# placa2caras_V1718.net
KiCad netlist of a schematic drawn in EAGLE
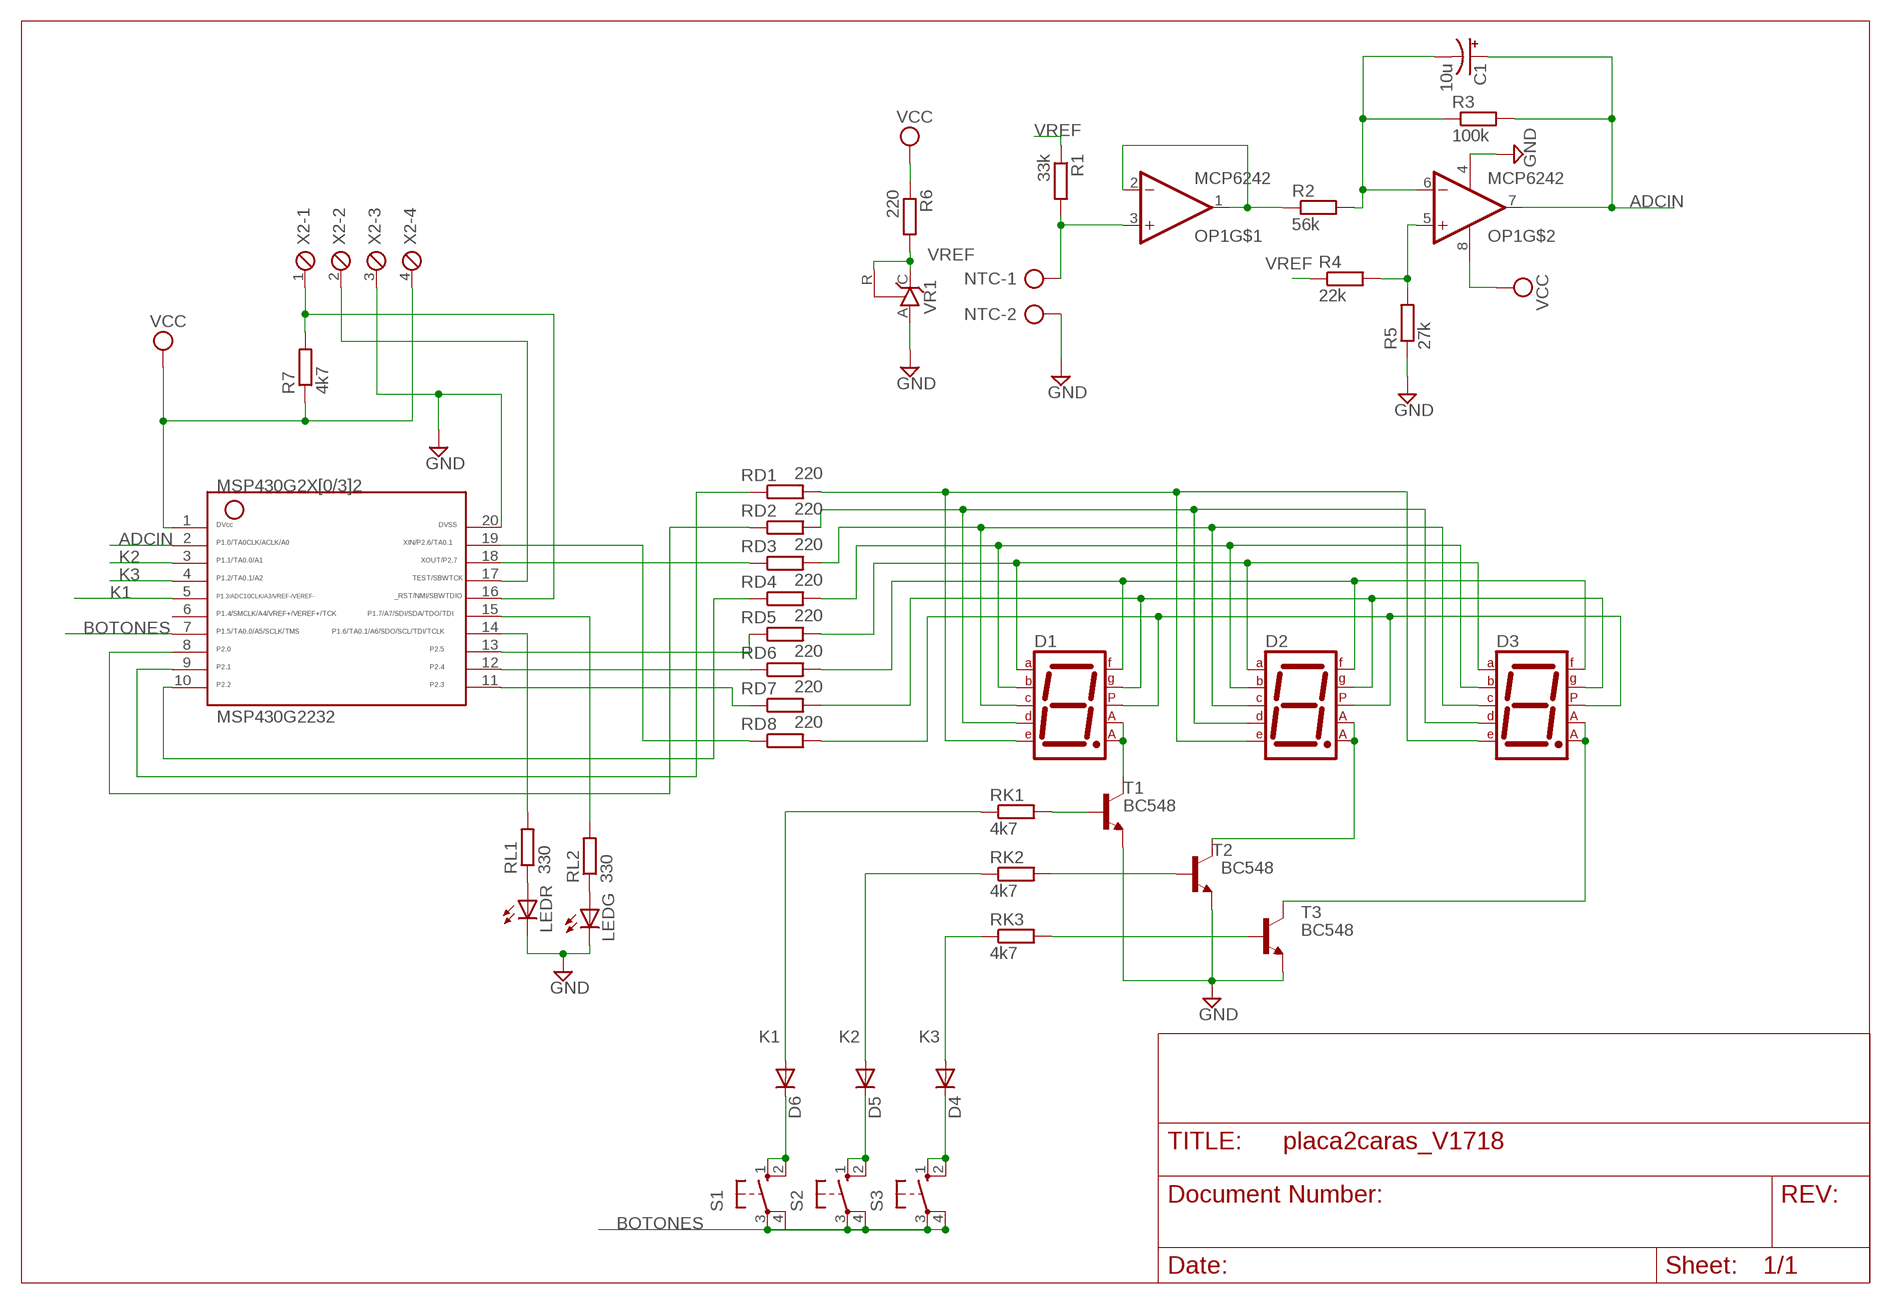
[diagram p0: schematic, sheet 1]

(export (version "E")
  (design (tool "Eeschema 10.0.6"))
  (components
    (comp (ref "C1")
      (value "10u")
      (footprint "eagle-import:E2,5-6E")
      (libsource (lib "eagle-import") (part "CPOL-USE2,5-6E"))
    )
    (comp (ref "D1")
      (value "7SEG-CA")
      (footprint "eagle-import:7SEG-13")
      (libsource (lib "eagle-import") (part "7SEG-CA"))
    )
    (comp (ref "D2")
      (value "7SEG-CA")
      (footprint "eagle-import:7SEG-13")
      (libsource (lib "eagle-import") (part "7SEG-CA"))
    )
    (comp (ref "D3")
      (value "7SEG-CA")
      (footprint "eagle-import:7SEG-13")
      (libsource (lib "eagle-import") (part "7SEG-CA"))
    )
    (comp (ref "D4")
      (value "1N4148DO35-10")
      (footprint "eagle-import:DO35-10")
      (libsource (lib "eagle-import") (part "1N4148DO35-10"))
    )
    (comp (ref "D5")
      (value "1N4148DO35-10")
      (footprint "eagle-import:DO35-10")
      (libsource (lib "eagle-import") (part "1N4148DO35-10"))
    )
    (comp (ref "D6")
      (value "1N4148DO35-10")
      (footprint "eagle-import:DO35-10")
      (libsource (lib "eagle-import") (part "1N4148DO35-10"))
    )
    (comp (ref "LEDG")
      (value "LED5MM")
      (footprint "eagle-import:LED5MM")
      (libsource (lib "eagle-import") (part "LED5MM"))
    )
    (comp (ref "LEDR")
      (value "LED5MM")
      (footprint "eagle-import:LED5MM")
      (libsource (lib "eagle-import") (part "LED5MM"))
    )
    (comp (ref "MSP430G2232")
      (value "G2X[0/3]2---N20")
      (footprint "eagle-import:N20")
      (libsource (lib "eagle-import") (part "G2X[0/3]2---N20"))
    )
    (comp (ref "NTC")
      (value "AK500/2")
      (footprint "eagle-import:AK500_2")
      (libsource (lib "eagle-import") (part "AK500/2"))
    )
    (comp (ref "OP1")
      (value "MCP6242")
      (footprint "eagle-import:DIL8_MOD")
      (libsource (lib "eagle-import") (part "MCP6242CONPADGORDO"))
    )
    (comp (ref "R1")
      (value "33k")
      (footprint "eagle-import:0207_10")
      (libsource (lib "eagle-import") (part "R-EU_0207/10"))
    )
    (comp (ref "R2")
      (value "56k")
      (footprint "eagle-import:0207_10")
      (libsource (lib "eagle-import") (part "R-EU_0207/10"))
    )
    (comp (ref "R3")
      (value "100k")
      (footprint "eagle-import:0207_10")
      (libsource (lib "eagle-import") (part "R-EU_0207/10"))
    )
    (comp (ref "R4")
      (value "22k")
      (footprint "eagle-import:0207_10")
      (libsource (lib "eagle-import") (part "R-EU_0207/10"))
    )
    (comp (ref "R5")
      (value "27k")
      (footprint "eagle-import:0207_10")
      (libsource (lib "eagle-import") (part "R-EU_0207/10"))
    )
    (comp (ref "R6")
      (value "220")
      (footprint "eagle-import:0207_10")
      (libsource (lib "eagle-import") (part "R-EU_0207/10"))
    )
    (comp (ref "R7")
      (value "4k7")
      (footprint "eagle-import:0207_10")
      (libsource (lib "eagle-import") (part "R-EU_0207/10"))
    )
    (comp (ref "RD1")
      (value "220")
      (footprint "eagle-import:0207_10")
      (libsource (lib "eagle-import") (part "R-EU_0207/10"))
    )
    (comp (ref "RD2")
      (value "220")
      (footprint "eagle-import:0207_10")
      (libsource (lib "eagle-import") (part "R-EU_0207/10"))
    )
    (comp (ref "RD3")
      (value "220")
      (footprint "eagle-import:0207_10")
      (libsource (lib "eagle-import") (part "R-EU_0207/10"))
    )
    (comp (ref "RD4")
      (value "220")
      (footprint "eagle-import:0207_10")
      (libsource (lib "eagle-import") (part "R-EU_0207/10"))
    )
    (comp (ref "RD5")
      (value "220")
      (footprint "eagle-import:0207_10")
      (libsource (lib "eagle-import") (part "R-EU_0207/10"))
    )
    (comp (ref "RD6")
      (value "220")
      (footprint "eagle-import:0207_10")
      (libsource (lib "eagle-import") (part "R-EU_0207/10"))
    )
    (comp (ref "RD7")
      (value "220")
      (footprint "eagle-import:0207_10")
      (libsource (lib "eagle-import") (part "R-EU_0207/10"))
    )
    (comp (ref "RD8")
      (value "220")
      (footprint "eagle-import:0207_10")
      (libsource (lib "eagle-import") (part "R-EU_0207/10"))
    )
    (comp (ref "RK1")
      (value "4k7")
      (footprint "eagle-import:0207_10")
      (libsource (lib "eagle-import") (part "R-EU_0207/10"))
    )
    (comp (ref "RK2")
      (value "4k7")
      (footprint "eagle-import:0207_10")
      (libsource (lib "eagle-import") (part "R-EU_0207/10"))
    )
    (comp (ref "RK3")
      (value "4k7")
      (footprint "eagle-import:0207_10")
      (libsource (lib "eagle-import") (part "R-EU_0207/10"))
    )
    (comp (ref "RL1")
      (value "330")
      (footprint "eagle-import:0207_10")
      (libsource (lib "eagle-import") (part "R-EU_0207/10"))
    )
    (comp (ref "RL2")
      (value "330")
      (footprint "eagle-import:0207_10")
      (libsource (lib "eagle-import") (part "R-EU_0207/10"))
    )
    (comp (ref "S1")
      (value "10-XX")
      (footprint "eagle-import:B3F-10XX")
      (fields (field (name "MPN") "B3F-1000"))
      (libsource (lib "eagle-import") (part "10-XX"))
    )
    (comp (ref "S2")
      (value "10-XX")
      (footprint "eagle-import:B3F-10XX")
      (fields (field (name "MPN") "B3F-1000"))
      (libsource (lib "eagle-import") (part "10-XX"))
    )
    (comp (ref "S3")
      (value "10-XX")
      (footprint "eagle-import:B3F-10XX")
      (fields (field (name "MPN") "B3F-1000"))
      (libsource (lib "eagle-import") (part "10-XX"))
    )
    (comp (ref "T1")
      (value "BC548")
      (footprint "eagle-import:TO92-EBC")
      (libsource (lib "eagle-import") (part "BC548"))
    )
    (comp (ref "T2")
      (value "BC548")
      (footprint "eagle-import:TO92-EBC")
      (libsource (lib "eagle-import") (part "BC548"))
    )
    (comp (ref "T3")
      (value "BC548")
      (footprint "eagle-import:TO92-EBC")
      (libsource (lib "eagle-import") (part "BC548"))
    )
    (comp (ref "VR1")
      (value "TL431CLP")
      (footprint "eagle-import:TO92-CLP")
      (libsource (lib "eagle-import") (part "TL431CLP"))
    )
    (comp (ref "X2")
      (value "MPT4")
      (footprint "eagle-import:4POL254")
      (libsource (lib "eagle-import") (part "MPT4"))
    )
  )
  (nets
    (net (code "1") (name "/ADCIN") (class "Default")
      (node (ref "C1") (pin "+") (pinfunction "+_+") (pintype "passive"))
      (node (ref "MSP430G2232") (pin "2") (pinfunction "2_2") (pintype "bidirectional"))
      (node (ref "OP1") (pin "7") (pinfunction "OUT_7") (pintype "output"))
      (node (ref "R3") (pin "2") (pinfunction "2_2") (pintype "passive"))
    )
    (net (code "2") (name "/BOTONES") (class "Default")
      (node (ref "MSP430G2232") (pin "7") (pinfunction "7_7") (pintype "bidirectional"))
      (node (ref "S1") (pin "3") (pinfunction "P_3") (pintype "passive"))
      (node (ref "S1") (pin "4") (pinfunction "P1_4") (pintype "passive"))
      (node (ref "S2") (pin "3") (pinfunction "P_3") (pintype "passive"))
      (node (ref "S2") (pin "4") (pinfunction "P1_4") (pintype "passive"))
      (node (ref "S3") (pin "3") (pinfunction "P_3") (pintype "passive"))
      (node (ref "S3") (pin "4") (pinfunction "P1_4") (pintype "passive"))
    )
    (net (code "3") (name "/K1") (class "Default")
      (node (ref "D6") (pin "A") (pinfunction "A_A") (pintype "passive"))
      (node (ref "MSP430G2232") (pin "5") (pinfunction "5_5") (pintype "bidirectional"))
      (node (ref "RK1") (pin "1") (pinfunction "1_1") (pintype "passive"))
    )
    (net (code "4") (name "/K2") (class "Default")
      (node (ref "D5") (pin "A") (pinfunction "A_A") (pintype "passive"))
      (node (ref "MSP430G2232") (pin "3") (pinfunction "3_3") (pintype "bidirectional"))
      (node (ref "RK2") (pin "1") (pinfunction "1_1") (pintype "passive"))
    )
    (net (code "5") (name "/K3") (class "Default")
      (node (ref "D4") (pin "A") (pinfunction "A_A") (pintype "passive"))
      (node (ref "MSP430G2232") (pin "4") (pinfunction "4_4") (pintype "bidirectional"))
      (node (ref "RK3") (pin "1") (pinfunction "1_1") (pintype "passive"))
    )
    (net (code "6") (name "/VREF") (class "Default")
      (node (ref "R1") (pin "1") (pinfunction "1_1") (pintype "passive"))
      (node (ref "R4") (pin "1") (pinfunction "1_1") (pintype "passive"))
      (node (ref "R6") (pin "2") (pinfunction "2_2") (pintype "passive"))
      (node (ref "VR1") (pin "C") (pinfunction "C_C") (pintype "passive"))
      (node (ref "VR1") (pin "R") (pinfunction "R_R") (pintype "passive"))
    )
    (net (code "7") (name "GND") (class "Default")
      (node (ref "LEDG") (pin "K") (pinfunction "C_K") (pintype "passive"))
      (node (ref "LEDR") (pin "K") (pinfunction "C_K") (pintype "passive"))
      (node (ref "MSP430G2232") (pin "20") (pinfunction "20_20") (pintype "bidirectional"))
      (node (ref "NTC") (pin "2") (pinfunction "KL_2") (pintype "passive"))
      (node (ref "OP1") (pin "4") (pinfunction "V-_4") (pintype "power_in"))
      (node (ref "R5") (pin "1") (pinfunction "1_1") (pintype "passive"))
      (node (ref "T1") (pin "E") (pinfunction "E_E") (pintype "passive"))
      (node (ref "T2") (pin "E") (pinfunction "E_E") (pintype "passive"))
      (node (ref "T3") (pin "E") (pinfunction "E_E") (pintype "passive"))
      (node (ref "VR1") (pin "A") (pinfunction "A_A") (pintype "passive"))
      (node (ref "X2") (pin "3") (pinfunction "1_3") (pintype "passive"))
    )
    (net (code "8") (name "Net-(D1-A)") (class "Default")
      (node (ref "D1") (pin "7") (pinfunction "A_7") (pintype "passive"))
      (node (ref "D2") (pin "7") (pinfunction "A_7") (pintype "passive"))
      (node (ref "D3") (pin "7") (pinfunction "A_7") (pintype "passive"))
      (node (ref "RD5") (pin "2") (pinfunction "2_2") (pintype "passive"))
    )
    (net (code "9") (name "Net-(D1-B)") (class "Default")
      (node (ref "D1") (pin "6") (pinfunction "B_6") (pintype "passive"))
      (node (ref "D2") (pin "6") (pinfunction "B_6") (pintype "passive"))
      (node (ref "D3") (pin "6") (pinfunction "B_6") (pintype "passive"))
      (node (ref "RD4") (pin "2") (pinfunction "2_2") (pintype "passive"))
    )
    (net (code "10") (name "Net-(D1-C)") (class "Default")
      (node (ref "D1") (pin "4") (pinfunction "C_4") (pintype "passive"))
      (node (ref "D2") (pin "4") (pinfunction "C_4") (pintype "passive"))
      (node (ref "D3") (pin "4") (pinfunction "C_4") (pintype "passive"))
      (node (ref "RD3") (pin "2") (pinfunction "2_2") (pintype "passive"))
    )
    (net (code "11") (name "Net-(D1-CA1)") (class "Default")
      (node (ref "D1") (pin "3") (pinfunction "CA1_3") (pintype "passive"))
      (node (ref "D1") (pin "8") (pinfunction "CA2_8") (pintype "passive"))
      (node (ref "T1") (pin "C") (pinfunction "C_C") (pintype "passive"))
    )
    (net (code "12") (name "Net-(D1-D)") (class "Default")
      (node (ref "D1") (pin "2") (pinfunction "D_2") (pintype "passive"))
      (node (ref "D2") (pin "2") (pinfunction "D_2") (pintype "passive"))
      (node (ref "D3") (pin "2") (pinfunction "D_2") (pintype "passive"))
      (node (ref "RD2") (pin "2") (pinfunction "2_2") (pintype "passive"))
    )
    (net (code "13") (name "Net-(D1-DP)") (class "Default")
      (node (ref "D1") (pin "5") (pinfunction "DP_5") (pintype "passive"))
      (node (ref "D2") (pin "5") (pinfunction "DP_5") (pintype "passive"))
      (node (ref "D3") (pin "5") (pinfunction "DP_5") (pintype "passive"))
      (node (ref "RD8") (pin "2") (pinfunction "2_2") (pintype "passive"))
    )
    (net (code "14") (name "Net-(D1-E)") (class "Default")
      (node (ref "D1") (pin "1") (pinfunction "E_1") (pintype "passive"))
      (node (ref "D2") (pin "1") (pinfunction "E_1") (pintype "passive"))
      (node (ref "D3") (pin "1") (pinfunction "E_1") (pintype "passive"))
      (node (ref "RD1") (pin "2") (pinfunction "2_2") (pintype "passive"))
    )
    (net (code "15") (name "Net-(D1-F)") (class "Default")
      (node (ref "D1") (pin "9") (pinfunction "F_9") (pintype "passive"))
      (node (ref "D2") (pin "9") (pinfunction "F_9") (pintype "passive"))
      (node (ref "D3") (pin "9") (pinfunction "F_9") (pintype "passive"))
      (node (ref "RD6") (pin "2") (pinfunction "2_2") (pintype "passive"))
    )
    (net (code "16") (name "Net-(D1-G)") (class "Default")
      (node (ref "D1") (pin "10") (pinfunction "G_10") (pintype "passive"))
      (node (ref "D2") (pin "10") (pinfunction "G_10") (pintype "passive"))
      (node (ref "D3") (pin "10") (pinfunction "G_10") (pintype "passive"))
      (node (ref "RD7") (pin "2") (pinfunction "2_2") (pintype "passive"))
    )
    (net (code "17") (name "Net-(D2-CA1)") (class "Default")
      (node (ref "D2") (pin "3") (pinfunction "CA1_3") (pintype "passive"))
      (node (ref "D2") (pin "8") (pinfunction "CA2_8") (pintype "passive"))
      (node (ref "T2") (pin "C") (pinfunction "C_C") (pintype "passive"))
    )
    (net (code "18") (name "Net-(D3-CA1)") (class "Default")
      (node (ref "D3") (pin "3") (pinfunction "CA1_3") (pintype "passive"))
      (node (ref "D3") (pin "8") (pinfunction "CA2_8") (pintype "passive"))
      (node (ref "T3") (pin "C") (pinfunction "C_C") (pintype "passive"))
    )
    (net (code "19") (name "Net-(LEDG-PadA)") (class "Default")
      (node (ref "LEDG") (pin "A") (pinfunction "A_A") (pintype "passive"))
      (node (ref "RL2") (pin "1") (pinfunction "1_1") (pintype "passive"))
    )
    (net (code "20") (name "Net-(LEDR-PadA)") (class "Default")
      (node (ref "LEDR") (pin "A") (pinfunction "A_A") (pintype "passive"))
      (node (ref "RL1") (pin "1") (pinfunction "1_1") (pintype "passive"))
    )
    (net (code "21") (name "Net-(MSP430G2232-Pad8)") (class "Default")
      (node (ref "MSP430G2232") (pin "8") (pinfunction "8_8") (pintype "bidirectional"))
      (node (ref "RD2") (pin "1") (pinfunction "1_1") (pintype "passive"))
    )
    (net (code "22") (name "Net-(MSP430G2232-Pad9)") (class "Default")
      (node (ref "MSP430G2232") (pin "9") (pinfunction "9_9") (pintype "bidirectional"))
      (node (ref "RD1") (pin "1") (pinfunction "1_1") (pintype "passive"))
    )
    (net (code "23") (name "Net-(MSP430G2232-Pad10)") (class "Default")
      (node (ref "MSP430G2232") (pin "10") (pinfunction "10_10") (pintype "bidirectional"))
      (node (ref "RD4") (pin "1") (pinfunction "1_1") (pintype "passive"))
    )
    (net (code "24") (name "Net-(MSP430G2232-Pad11)") (class "Default")
      (node (ref "MSP430G2232") (pin "11") (pinfunction "11_11") (pintype "bidirectional"))
      (node (ref "RD7") (pin "1") (pinfunction "1_1") (pintype "passive"))
    )
    (net (code "25") (name "Net-(MSP430G2232-Pad12)") (class "Default")
      (node (ref "MSP430G2232") (pin "12") (pinfunction "12_12") (pintype "bidirectional"))
      (node (ref "RD6") (pin "1") (pinfunction "1_1") (pintype "passive"))
    )
    (net (code "26") (name "Net-(MSP430G2232-Pad13)") (class "Default")
      (node (ref "MSP430G2232") (pin "13") (pinfunction "13_13") (pintype "bidirectional"))
      (node (ref "RD5") (pin "1") (pinfunction "1_1") (pintype "passive"))
    )
    (net (code "27") (name "Net-(MSP430G2232-Pad14)") (class "Default")
      (node (ref "MSP430G2232") (pin "14") (pinfunction "14_14") (pintype "bidirectional"))
      (node (ref "RL1") (pin "2") (pinfunction "2_2") (pintype "passive"))
    )
    (net (code "28") (name "Net-(MSP430G2232-Pad15)") (class "Default")
      (node (ref "MSP430G2232") (pin "15") (pinfunction "15_15") (pintype "bidirectional"))
      (node (ref "RL2") (pin "2") (pinfunction "2_2") (pintype "passive"))
    )
    (net (code "29") (name "Net-(MSP430G2232-Pad16)") (class "Default")
      (node (ref "MSP430G2232") (pin "16") (pinfunction "16_16") (pintype "bidirectional"))
      (node (ref "R7") (pin "2") (pinfunction "2_2") (pintype "passive"))
      (node (ref "X2") (pin "1") (pinfunction "1_1") (pintype "passive"))
    )
    (net (code "30") (name "Net-(MSP430G2232-Pad18)") (class "Default")
      (node (ref "MSP430G2232") (pin "18") (pinfunction "18_18") (pintype "bidirectional"))
      (node (ref "RD3") (pin "1") (pinfunction "1_1") (pintype "passive"))
    )
    (net (code "31") (name "Net-(MSP430G2232-Pad19)") (class "Default")
      (node (ref "MSP430G2232") (pin "19") (pinfunction "19_19") (pintype "bidirectional"))
      (node (ref "RD8") (pin "1") (pinfunction "1_1") (pintype "passive"))
    )
    (net (code "32") (name "Net-(NTCA-KL)") (class "Default")
      (node (ref "NTC") (pin "1") (pinfunction "KL_1") (pintype "passive"))
      (node (ref "OP1") (pin "3") (pinfunction "+IN_3") (pintype "input"))
      (node (ref "R1") (pin "2") (pinfunction "2_2") (pintype "passive"))
    )
    (net (code "33") (name "Net-(OP1A--IN)") (class "Default")
      (node (ref "OP1") (pin "1") (pinfunction "OUT_1") (pintype "output"))
      (node (ref "OP1") (pin "2") (pinfunction "-IN_2") (pintype "input"))
      (node (ref "R2") (pin "1") (pinfunction "1_1") (pintype "passive"))
    )
    (net (code "34") (name "Net-(OP1B-+IN)") (class "Default")
      (node (ref "OP1") (pin "5") (pinfunction "+IN_5") (pintype "input"))
      (node (ref "R4") (pin "2") (pinfunction "2_2") (pintype "passive"))
      (node (ref "R5") (pin "2") (pinfunction "2_2") (pintype "passive"))
    )
    (net (code "35") (name "Net-(OP1B--IN)") (class "Default")
      (node (ref "C1") (pin "-") (pinfunction "-_-") (pintype "passive"))
      (node (ref "OP1") (pin "6") (pinfunction "-IN_6") (pintype "input"))
      (node (ref "R2") (pin "2") (pinfunction "2_2") (pintype "passive"))
      (node (ref "R3") (pin "1") (pinfunction "1_1") (pintype "passive"))
    )
    (net (code "36") (name "Net-(RK1-Pad2)") (class "Default")
      (node (ref "RK1") (pin "2") (pinfunction "2_2") (pintype "passive"))
      (node (ref "T1") (pin "B") (pinfunction "B_B") (pintype "passive"))
    )
    (net (code "37") (name "Net-(RK2-Pad2)") (class "Default")
      (node (ref "RK2") (pin "2") (pinfunction "2_2") (pintype "passive"))
      (node (ref "T2") (pin "B") (pinfunction "B_B") (pintype "passive"))
    )
    (net (code "38") (name "Net-(RK3-Pad2)") (class "Default")
      (node (ref "RK3") (pin "2") (pinfunction "2_2") (pintype "passive"))
      (node (ref "T3") (pin "B") (pinfunction "B_B") (pintype "passive"))
    )
    (net (code "39") (name "Net-(S1-S)") (class "Default")
      (node (ref "D6") (pin "C") (pinfunction "C_C") (pintype "passive"))
      (node (ref "S1") (pin "1") (pinfunction "S_1") (pintype "passive"))
      (node (ref "S1") (pin "2") (pinfunction "S1_2") (pintype "passive"))
    )
    (net (code "40") (name "Net-(S2-S)") (class "Default")
      (node (ref "D5") (pin "C") (pinfunction "C_C") (pintype "passive"))
      (node (ref "S2") (pin "1") (pinfunction "S_1") (pintype "passive"))
      (node (ref "S2") (pin "2") (pinfunction "S1_2") (pintype "passive"))
    )
    (net (code "41") (name "Net-(S3-S)") (class "Default")
      (node (ref "D4") (pin "C") (pinfunction "C_C") (pintype "passive"))
      (node (ref "S3") (pin "1") (pinfunction "S_1") (pintype "passive"))
      (node (ref "S3") (pin "2") (pinfunction "S1_2") (pintype "passive"))
    )
    (net (code "42") (name "Net-(X2B-1)") (class "Default")
      (node (ref "MSP430G2232") (pin "17") (pinfunction "17_17") (pintype "bidirectional"))
      (node (ref "X2") (pin "2") (pinfunction "1_2") (pintype "passive"))
    )
    (net (code "43") (name "VCC") (class "Default")
      (node (ref "MSP430G2232") (pin "1") (pinfunction "1_1") (pintype "bidirectional"))
      (node (ref "OP1") (pin "8") (pinfunction "V+_8") (pintype "power_in"))
      (node (ref "R6") (pin "1") (pinfunction "1_1") (pintype "passive"))
      (node (ref "R7") (pin "1") (pinfunction "1_1") (pintype "passive"))
      (node (ref "X2") (pin "4") (pinfunction "1_4") (pintype "passive"))
    )
    (net (code "44") (name "unconnected-(MSP430G2232-Pad6)") (class "Default")
      (node (ref "MSP430G2232") (pin "6") (pinfunction "6_6") (pintype "bidirectional"))
    )
  )
)
